# SparkX_EZ_Header.net
KiCad netlist of a schematic drawn in EAGLE
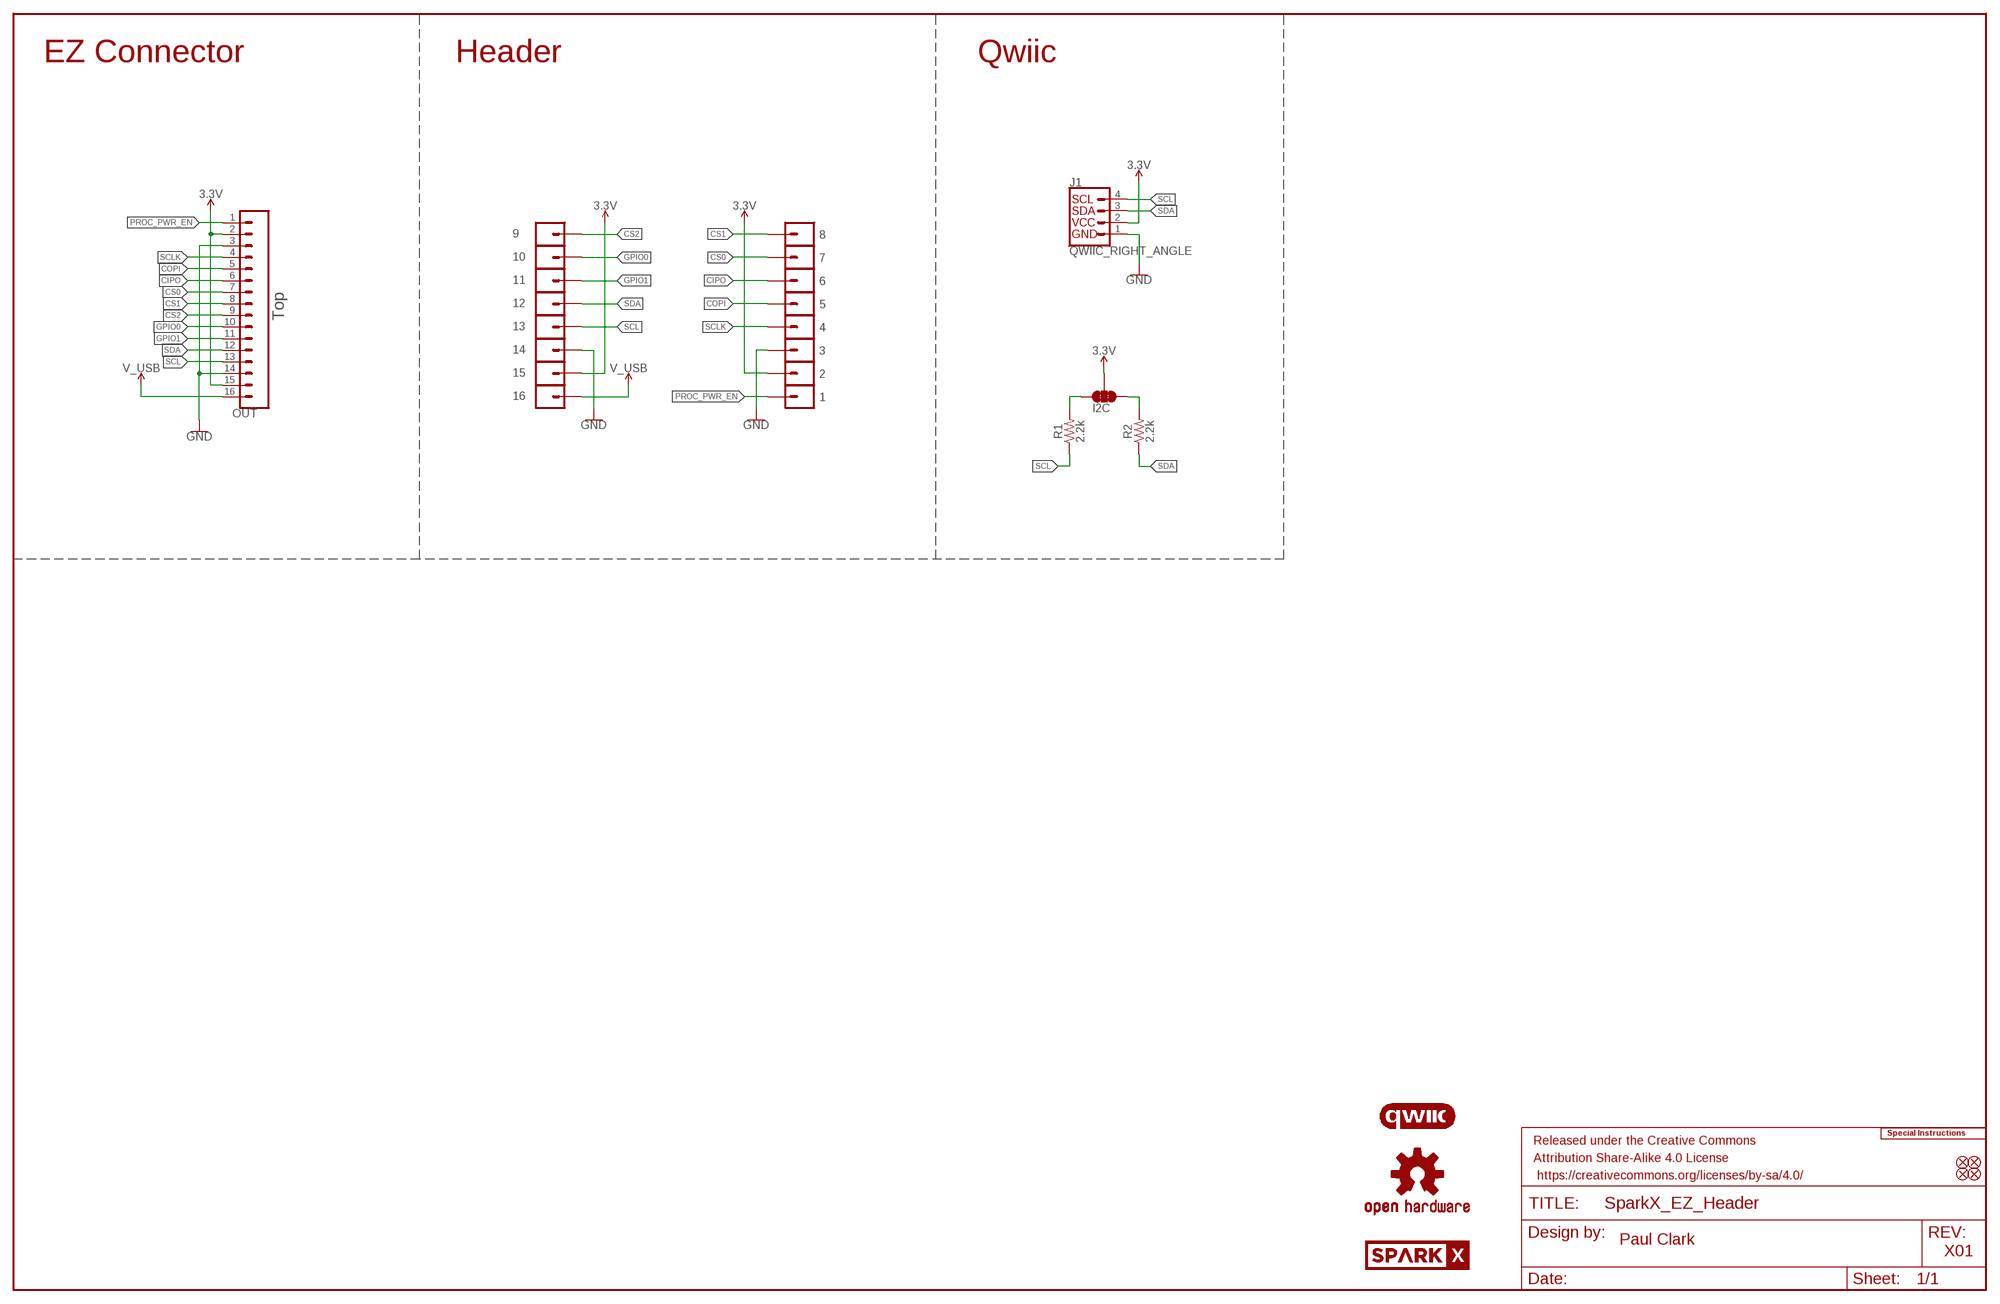
[diagram p0: schematic, sheet 1]

(export (version "E")
  (design (tool "Eeschema 10.0.6"))
  (components
    (comp (ref "1")
      (value "CONN_01PTH_NO_SILK_YES_STOP")
      (footprint "eagle-import:1X01_NO_SILK")
      (libsource (lib "eagle-import") (part "CONN_01PTH_NO_SILK_YES_STOP"))
    )
    (comp (ref "2")
      (value "CONN_01PTH_NO_SILK_YES_STOP")
      (footprint "eagle-import:1X01_NO_SILK")
      (libsource (lib "eagle-import") (part "CONN_01PTH_NO_SILK_YES_STOP"))
    )
    (comp (ref "3")
      (value "CONN_01PTH_NO_SILK_YES_STOP")
      (footprint "eagle-import:1X01_NO_SILK")
      (libsource (lib "eagle-import") (part "CONN_01PTH_NO_SILK_YES_STOP"))
    )
    (comp (ref "4")
      (value "CONN_01PTH_NO_SILK_YES_STOP")
      (footprint "eagle-import:1X01_NO_SILK")
      (libsource (lib "eagle-import") (part "CONN_01PTH_NO_SILK_YES_STOP"))
    )
    (comp (ref "5")
      (value "CONN_01PTH_NO_SILK_YES_STOP")
      (footprint "eagle-import:1X01_NO_SILK")
      (libsource (lib "eagle-import") (part "CONN_01PTH_NO_SILK_YES_STOP"))
    )
    (comp (ref "6")
      (value "CONN_01PTH_NO_SILK_YES_STOP")
      (footprint "eagle-import:1X01_NO_SILK")
      (libsource (lib "eagle-import") (part "CONN_01PTH_NO_SILK_YES_STOP"))
    )
    (comp (ref "7")
      (value "CONN_01PTH_NO_SILK_YES_STOP")
      (footprint "eagle-import:1X01_NO_SILK")
      (libsource (lib "eagle-import") (part "CONN_01PTH_NO_SILK_YES_STOP"))
    )
    (comp (ref "8")
      (value "CONN_01PTH_NO_SILK_YES_STOP")
      (footprint "eagle-import:1X01_NO_SILK")
      (libsource (lib "eagle-import") (part "CONN_01PTH_NO_SILK_YES_STOP"))
    )
    (comp (ref "9")
      (value "CONN_01PTH_NO_SILK_YES_STOP")
      (footprint "eagle-import:1X01_NO_SILK")
      (libsource (lib "eagle-import") (part "CONN_01PTH_NO_SILK_YES_STOP"))
    )
    (comp (ref "10")
      (value "CONN_01PTH_NO_SILK_YES_STOP")
      (footprint "eagle-import:1X01_NO_SILK")
      (libsource (lib "eagle-import") (part "CONN_01PTH_NO_SILK_YES_STOP"))
    )
    (comp (ref "11")
      (value "CONN_01PTH_NO_SILK_YES_STOP")
      (footprint "eagle-import:1X01_NO_SILK")
      (libsource (lib "eagle-import") (part "CONN_01PTH_NO_SILK_YES_STOP"))
    )
    (comp (ref "12")
      (value "CONN_01PTH_NO_SILK_YES_STOP")
      (footprint "eagle-import:1X01_NO_SILK")
      (libsource (lib "eagle-import") (part "CONN_01PTH_NO_SILK_YES_STOP"))
    )
    (comp (ref "13")
      (value "CONN_01PTH_NO_SILK_YES_STOP")
      (footprint "eagle-import:1X01_NO_SILK")
      (libsource (lib "eagle-import") (part "CONN_01PTH_NO_SILK_YES_STOP"))
    )
    (comp (ref "14")
      (value "CONN_01PTH_NO_SILK_YES_STOP")
      (footprint "eagle-import:1X01_NO_SILK")
      (libsource (lib "eagle-import") (part "CONN_01PTH_NO_SILK_YES_STOP"))
    )
    (comp (ref "15")
      (value "CONN_01PTH_NO_SILK_YES_STOP")
      (footprint "eagle-import:1X01_NO_SILK")
      (libsource (lib "eagle-import") (part "CONN_01PTH_NO_SILK_YES_STOP"))
    )
    (comp (ref "16")
      (value "CONN_01PTH_NO_SILK_YES_STOP")
      (footprint "eagle-import:1X01_NO_SILK")
      (libsource (lib "eagle-import") (part "CONN_01PTH_NO_SILK_YES_STOP"))
    )
    (comp (ref "FD1")
      (value "FIDUCIALUFIDUCIAL")
      (footprint "eagle-import:FIDUCIAL-MICRO")
      (libsource (lib "eagle-import") (part "FIDUCIALUFIDUCIAL"))
    )
    (comp (ref "FD2")
      (value "FIDUCIALUFIDUCIAL")
      (footprint "eagle-import:FIDUCIAL-MICRO")
      (libsource (lib "eagle-import") (part "FIDUCIALUFIDUCIAL"))
    )
    (comp (ref "FD3")
      (value "FIDUCIALUFIDUCIAL")
      (footprint "eagle-import:FIDUCIAL-MICRO")
      (libsource (lib "eagle-import") (part "FIDUCIALUFIDUCIAL"))
    )
    (comp (ref "FD4")
      (value "FIDUCIALUFIDUCIAL")
      (footprint "eagle-import:FIDUCIAL-MICRO")
      (libsource (lib "eagle-import") (part "FIDUCIALUFIDUCIAL"))
    )
    (comp (ref "FRAME1")
      (value "FRAME-LEDGER")
      (footprint "eagle-import:CREATIVE_COMMONS")
      (libsource (lib "eagle-import") (part "FRAME-LEDGER"))
    )
    (comp (ref "I2C")
      (value "JUMPER-SMT_3_2-NC_TRACE_SILK")
      (footprint "eagle-import:SMT-JUMPER_3_2-NC_TRACE_SILK")
      (libsource (lib "eagle-import") (part "JUMPER-SMT_3_2-NC_TRACE_SILK"))
    )
    (comp (ref "J1")
      (value "QWIIC_RIGHT_ANGLE")
      (footprint "eagle-import:JST04_1MM_RA")
      (libsource (lib "eagle-import") (part "QWIIC_CONNECTORJS-1MM"))
    )
    (comp (ref "LOGO1")
      (value "SPECIAL_INSTRUCTIONS-ORDERING")
      (footprint "eagle-import:ORDERING_INSTRUCTIONS")
      (libsource (lib "eagle-import") (part "SPECIAL_INSTRUCTIONS-ORDERING"))
    )
    (comp (ref "LOGO2")
      (value "OSHW-LOGOMINI")
      (footprint "eagle-import:OSHW-LOGO-MINI")
      (libsource (lib "eagle-import") (part "OSHW-LOGOMINI"))
    )
    (comp (ref "LOGO3")
      (value "OSHW-LOGOMINI")
      (footprint "eagle-import:OSHW-LOGO-MINI")
      (libsource (lib "eagle-import") (part "OSHW-LOGOMINI"))
    )
    (comp (ref "LOGO4")
      (value "QWIIC_LOGO_5MM")
      (footprint "eagle-import:QWIIC_5MM")
      (libsource (lib "eagle-import") (part "QWIIC_LOGO_5MM"))
    )
    (comp (ref "OUT")
      (value "CONN_16FPC_16_0.5MM")
      (footprint "eagle-import:FPC_16_0.5MM")
      (libsource (lib "eagle-import") (part "CONN_16FPC_16_0.5MM"))
    )
    (comp (ref "R1")
      (value "2.2k")
      (footprint "eagle-import:0603")
      (libsource (lib "eagle-import") (part "2.2KOHM-0603-1/10W-1%"))
    )
    (comp (ref "R2")
      (value "2.2k")
      (footprint "eagle-import:0603")
      (libsource (lib "eagle-import") (part "2.2KOHM-0603-1/10W-1%"))
    )
    (comp (ref "U$1")
      (value "SPARKX-LOGO3")
      (footprint "eagle-import:SPARKX-SMALL")
      (libsource (lib "eagle-import") (part "SPARKX-LOGO3"))
    )
  )
  (nets
    (net (code "1") (name "3.3V") (class "Default")
      (node (ref "15") (pin "1") (pinfunction "1_1") (pintype "passive"))
      (node (ref "2") (pin "1") (pinfunction "1_1") (pintype "passive"))
      (node (ref "I2C") (pin "2") (pinfunction "2_2") (pintype "passive"))
      (node (ref "J1") (pin "2") (pinfunction "2_2") (pintype "power_in"))
      (node (ref "OUT") (pin "15") (pinfunction "15_15") (pintype "passive"))
      (node (ref "OUT") (pin "2") (pinfunction "2_2") (pintype "passive"))
    )
    (net (code "2") (name "CIPO") (class "Default")
      (node (ref "6") (pin "1") (pinfunction "1_1") (pintype "passive"))
      (node (ref "OUT") (pin "6") (pinfunction "6_6") (pintype "passive"))
    )
    (net (code "3") (name "COPI") (class "Default")
      (node (ref "5") (pin "1") (pinfunction "1_1") (pintype "passive"))
      (node (ref "OUT") (pin "5") (pinfunction "5_5") (pintype "passive"))
    )
    (net (code "4") (name "CS0") (class "Default")
      (node (ref "7") (pin "1") (pinfunction "1_1") (pintype "passive"))
      (node (ref "OUT") (pin "7") (pinfunction "7_7") (pintype "passive"))
    )
    (net (code "5") (name "CS1") (class "Default")
      (node (ref "8") (pin "1") (pinfunction "1_1") (pintype "passive"))
      (node (ref "OUT") (pin "8") (pinfunction "8_8") (pintype "passive"))
    )
    (net (code "6") (name "CS2") (class "Default")
      (node (ref "9") (pin "1") (pinfunction "1_1") (pintype "passive"))
      (node (ref "OUT") (pin "9") (pinfunction "9_9") (pintype "passive"))
    )
    (net (code "7") (name "GND") (class "Default")
      (node (ref "14") (pin "1") (pinfunction "1_1") (pintype "passive"))
      (node (ref "3") (pin "1") (pinfunction "1_1") (pintype "passive"))
      (node (ref "J1") (pin "1") (pinfunction "1_1") (pintype "power_in"))
      (node (ref "OUT") (pin "14") (pinfunction "14_14") (pintype "passive"))
      (node (ref "OUT") (pin "3") (pinfunction "3_3") (pintype "passive"))
    )
    (net (code "8") (name "GPIO0") (class "Default")
      (node (ref "10") (pin "1") (pinfunction "1_1") (pintype "passive"))
      (node (ref "OUT") (pin "10") (pinfunction "10_10") (pintype "passive"))
    )
    (net (code "9") (name "GPIO1") (class "Default")
      (node (ref "11") (pin "1") (pinfunction "1_1") (pintype "passive"))
      (node (ref "OUT") (pin "11") (pinfunction "11_11") (pintype "passive"))
    )
    (net (code "10") (name "Net-(I2C-Pad1)") (class "Default")
      (node (ref "I2C") (pin "1") (pinfunction "1_1") (pintype "passive"))
      (node (ref "R2") (pin "2") (pinfunction "2_2") (pintype "passive"))
    )
    (net (code "11") (name "Net-(I2C-Pad3)") (class "Default")
      (node (ref "I2C") (pin "3") (pinfunction "3_3") (pintype "passive"))
      (node (ref "R1") (pin "2") (pinfunction "2_2") (pintype "passive"))
    )
    (net (code "12") (name "PROC_PWR_EN") (class "Default")
      (node (ref "1") (pin "1") (pinfunction "1_1") (pintype "passive"))
      (node (ref "OUT") (pin "1") (pinfunction "1_1") (pintype "passive"))
    )
    (net (code "13") (name "SCL") (class "Default")
      (node (ref "13") (pin "1") (pinfunction "1_1") (pintype "passive"))
      (node (ref "J1") (pin "4") (pinfunction "4_4") (pintype "passive"))
      (node (ref "OUT") (pin "13") (pinfunction "13_13") (pintype "passive"))
      (node (ref "R1") (pin "1") (pinfunction "1_1") (pintype "passive"))
    )
    (net (code "14") (name "SCLK") (class "Default")
      (node (ref "4") (pin "1") (pinfunction "1_1") (pintype "passive"))
      (node (ref "OUT") (pin "4") (pinfunction "4_4") (pintype "passive"))
    )
    (net (code "15") (name "SDA") (class "Default")
      (node (ref "12") (pin "1") (pinfunction "1_1") (pintype "passive"))
      (node (ref "J1") (pin "3") (pinfunction "3_3") (pintype "passive"))
      (node (ref "OUT") (pin "12") (pinfunction "12_12") (pintype "passive"))
      (node (ref "R2") (pin "1") (pinfunction "1_1") (pintype "passive"))
    )
    (net (code "16") (name "V_USB") (class "Default")
      (node (ref "16") (pin "1") (pinfunction "1_1") (pintype "passive"))
      (node (ref "OUT") (pin "16") (pinfunction "16_16") (pintype "passive"))
    )
  )
)
